# DW1000.net
KiCad netlist of a schematic drawn in Altium Designer
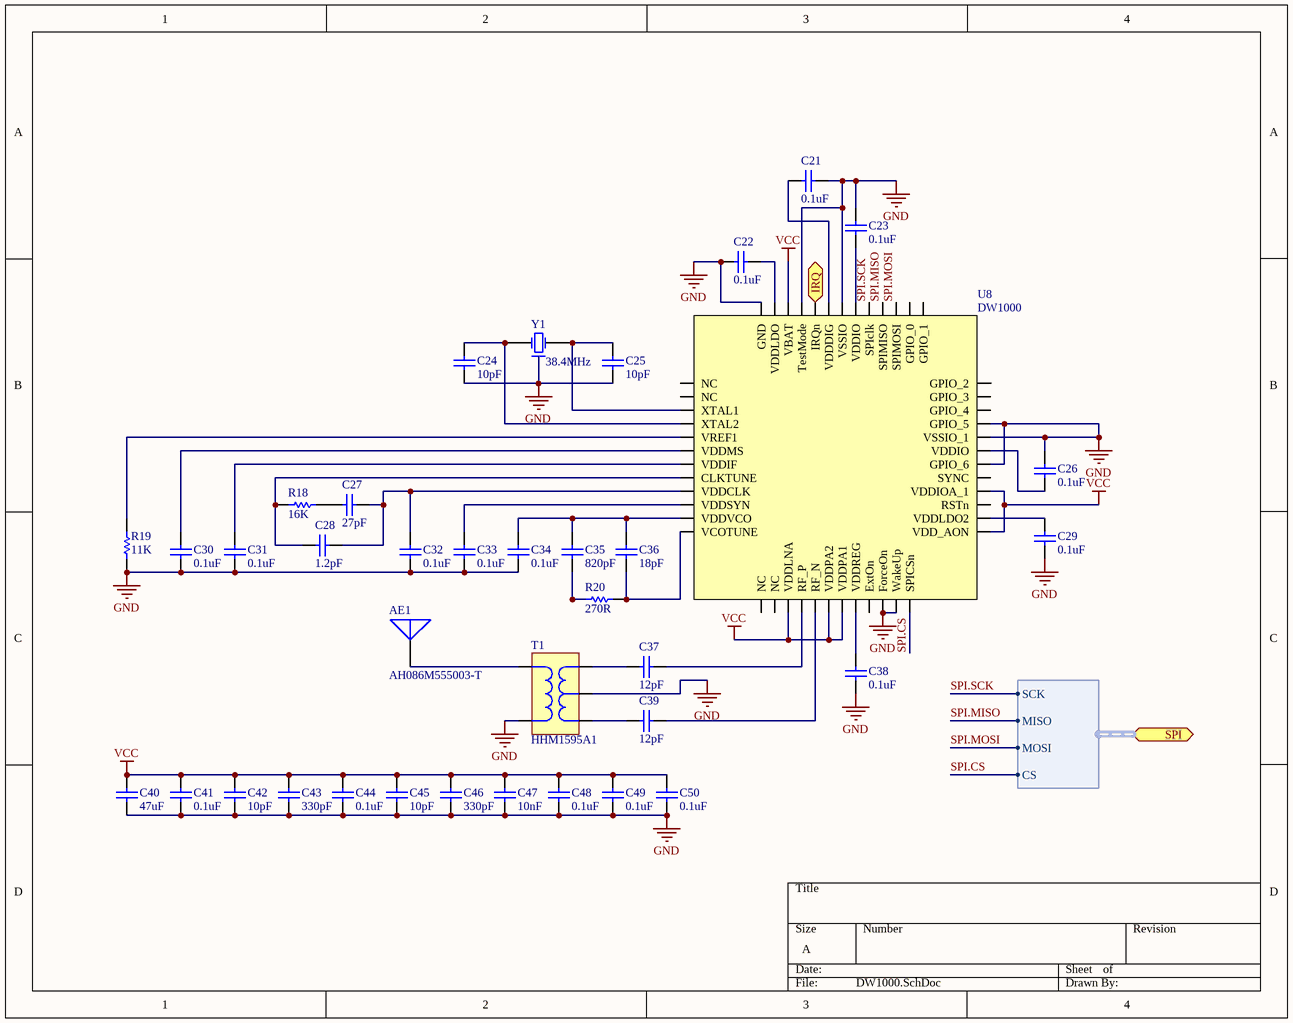
[diagram p0: DW1000.SchDoc]

(export (version "E")
  (design (tool "Eeschema 10.0.6"))
  (components
    (comp (ref "AE1")
      (value "AH086M555003-T")
      (footprint "AH086M555003-T")
      (fields (field (name "MANUFACTURER") "Taiyo Yuden"))
      (libsource (lib "Components") (part "AH086M555003-T"))
    )
    (comp (ref "C21")
      (value "0.1uF")
      (footprint "C0402[1005X55]")
      (description "0.1uF 6.3V 10% 0402 (1005 Metric)")
      (fields (field (name "PARTNUMBER") "GRM155R70J104KA01D") (field (name "MANUFACTURER") "Murata"))
      (libsource (lib "Capacitors") (part "CAP_0.1uF_6.3V_0402_10%"))
    )
    (comp (ref "C22")
      (value "0.1uF")
      (footprint "C0402[1005X55]")
      (description "0.1uF 6.3V 10% 0402 (1005 Metric)")
      (fields (field (name "PARTNUMBER") "GRM155R70J104KA01D") (field (name "MANUFACTURER") "Murata"))
      (libsource (lib "Capacitors") (part "CAP_0.1uF_6.3V_0402_10%"))
    )
    (comp (ref "C23")
      (value "0.1uF")
      (footprint "C0402[1005X55]")
      (description "0.1uF 6.3V 10% 0402 (1005 Metric)")
      (fields (field (name "PARTNUMBER") "GRM155R70J104KA01D") (field (name "MANUFACTURER") "Murata"))
      (libsource (lib "Capacitors") (part "CAP_0.1uF_6.3V_0402_10%"))
    )
    (comp (ref "C24")
      (value "10pF")
      (footprint "C0402[1005X55]")
      (description "10pF 50V 1% 0402 (1005 Metric)")
      (fields (field (name "PARTNUMBER") "GRM1555C1H100FA01D") (field (name "MANUFACTURER") "Murata"))
      (libsource (lib "Capacitors") (part "CAP_10pF_50V_0402_1%"))
    )
    (comp (ref "C25")
      (value "10pF")
      (footprint "C0402[1005X55]")
      (description "10pF 50V 1% 0402 (1005 Metric)")
      (fields (field (name "PARTNUMBER") "GRM1555C1H100FA01D") (field (name "MANUFACTURER") "Murata"))
      (libsource (lib "Capacitors") (part "CAP_10pF_50V_0402_1%"))
    )
    (comp (ref "C26")
      (value "0.1uF")
      (footprint "C0402[1005X55]")
      (description "0.1uF 6.3V 10% 0402 (1005 Metric)")
      (fields (field (name "PARTNUMBER") "GRM155R70J104KA01D") (field (name "MANUFACTURER") "Murata"))
      (libsource (lib "Capacitors") (part "CAP_0.1uF_6.3V_0402_10%"))
    )
    (comp (ref "C27")
      (value "27pF")
      (footprint "C0402[1005X55]")
      (description "27pF 50V 1% 0402 (1005 Metric)")
      (fields (field (name "PARTNUMBER") "GRM1555C1H270FA01D") (field (name "MANUFACTURER") "Murata"))
      (libsource (lib "Capacitors") (part "CAP_27pF_50V_0402_1%"))
    )
    (comp (ref "C28")
      (value "1.2pF")
      (footprint "C0402[1005X55]")
      (description "1.2pF 50V 0.05pF 0402 (1005 Metric)")
      (fields (field (name "PARTNUMBER") "GRM1555C1H1R2WA01D") (field (name "MANUFACTURER") "Murata"))
      (libsource (lib "Capacitors") (part "CAP_1.2pF_50V_0402_0.05pF"))
    )
    (comp (ref "C29")
      (value "0.1uF")
      (footprint "C0402[1005X55]")
      (description "0.1uF 6.3V 10% 0402 (1005 Metric)")
      (fields (field (name "PARTNUMBER") "GRM155R70J104KA01D") (field (name "MANUFACTURER") "Murata"))
      (libsource (lib "Capacitors") (part "CAP_0.1uF_6.3V_0402_10%"))
    )
    (comp (ref "C30")
      (value "0.1uF")
      (footprint "C0402[1005X55]")
      (description "0.1uF 6.3V 10% 0402 (1005 Metric)")
      (fields (field (name "PARTNUMBER") "GRM155R70J104KA01D") (field (name "MANUFACTURER") "Murata"))
      (libsource (lib "Capacitors") (part "CAP_0.1uF_6.3V_0402_10%"))
    )
    (comp (ref "C31")
      (value "0.1uF")
      (footprint "C0402[1005X55]")
      (description "0.1uF 6.3V 10% 0402 (1005 Metric)")
      (fields (field (name "PARTNUMBER") "GRM155R70J104KA01D") (field (name "MANUFACTURER") "Murata"))
      (libsource (lib "Capacitors") (part "CAP_0.1uF_6.3V_0402_10%"))
    )
    (comp (ref "C32")
      (value "0.1uF")
      (footprint "C0402[1005X55]")
      (description "0.1uF 6.3V 10% 0402 (1005 Metric)")
      (fields (field (name "PARTNUMBER") "GRM155R70J104KA01D") (field (name "MANUFACTURER") "Murata"))
      (libsource (lib "Capacitors") (part "CAP_0.1uF_6.3V_0402_10%"))
    )
    (comp (ref "C33")
      (value "0.1uF")
      (footprint "C0402[1005X55]")
      (description "0.1uF 6.3V 10% 0402 (1005 Metric)")
      (fields (field (name "PARTNUMBER") "GRM155R70J104KA01D") (field (name "MANUFACTURER") "Murata"))
      (libsource (lib "Capacitors") (part "CAP_0.1uF_6.3V_0402_10%"))
    )
    (comp (ref "C34")
      (value "0.1uF")
      (footprint "C0402[1005X55]")
      (description "0.1uF 6.3V 10% 0402 (1005 Metric)")
      (fields (field (name "PARTNUMBER") "GRM155R70J104KA01D") (field (name "MANUFACTURER") "Murata"))
      (libsource (lib "Capacitors") (part "CAP_0.1uF_6.3V_0402_10%"))
    )
    (comp (ref "C35")
      (value "820pF")
      (footprint "C0402[1005X55]")
      (description "820pF 50V 5% 0402 (1005 Metric)")
      (fields (field (name "PARTNUMBER") "GRM1555C1H821JA01D") (field (name "MANUFACTURER") "Murata"))
      (libsource (lib "Capacitors") (part "CAP_820pF_50V_0402_5%"))
    )
    (comp (ref "C36")
      (value "18pF")
      (footprint "C0402[1005X55]")
      (description "18pF 50V 1% 0402 (1005 Metric)")
      (fields (field (name "PARTNUMBER") "GRM1555C1H180FA01D") (field (name "MANUFACTURER") "Murata"))
      (libsource (lib "Capacitors") (part "CAP_18pF_50V_0402_1%"))
    )
    (comp (ref "C37")
      (value "12pF")
      (footprint "C0402[1005X55]")
      (description "12pF 50V 5% 0402 (1005 Metric)")
      (fields (field (name "PARTNUMBER") "GRM1555C1H120JA01D") (field (name "MANUFACTURER") "Murata"))
      (libsource (lib "Capacitors") (part "CAP_12pF_50V_0402_5%"))
    )
    (comp (ref "C38")
      (value "0.1uF")
      (footprint "C0402[1005X55]")
      (description "0.1uF 6.3V 10% 0402 (1005 Metric)")
      (fields (field (name "PARTNUMBER") "GRM155R70J104KA01D") (field (name "MANUFACTURER") "Murata"))
      (libsource (lib "Capacitors") (part "CAP_0.1uF_6.3V_0402_10%"))
    )
    (comp (ref "C39")
      (value "12pF")
      (footprint "C0402[1005X55]")
      (description "12pF 50V 5% 0402 (1005 Metric)")
      (fields (field (name "PARTNUMBER") "GRM1555C1H120JA01D") (field (name "MANUFACTURER") "Murata"))
      (libsource (lib "Capacitors") (part "CAP_12pF_50V_0402_5%"))
    )
    (comp (ref "C40")
      (value "47uF")
      (footprint "C1206[3216X160]")
      (description "47uF 6.3V 10% 1206 (3216 Metric)")
      (fields (field (name "PARTNUMBER") "GRM31CR60J476KE19L") (field (name "MANUFACTURER") "Murata"))
      (libsource (lib "Capacitors") (part "CAP_47uF_6.3V_1206_10%"))
    )
    (comp (ref "C41")
      (value "0.1uF")
      (footprint "C0402[1005X55]")
      (description "0.1uF 6.3V 10% 0402 (1005 Metric)")
      (fields (field (name "PARTNUMBER") "GRM155R70J104KA01D") (field (name "MANUFACTURER") "Murata"))
      (libsource (lib "Capacitors") (part "CAP_0.1uF_6.3V_0402_10%"))
    )
    (comp (ref "C42")
      (value "10pF")
      (footprint "C0402[1005X55]")
      (description "10pF 50V 1% 0402 (1005 Metric)")
      (fields (field (name "PARTNUMBER") "GRM1555C1H100FA01D") (field (name "MANUFACTURER") "Murata"))
      (libsource (lib "Capacitors") (part "CAP_10pF_50V_0402_1%"))
    )
    (comp (ref "C43")
      (value "330pF")
      (footprint "C0402[1005X55]")
      (description "330pF 50V 5% 0402 (1005 Metric)")
      (fields (field (name "PARTNUMBER") "GRM1555C1H331JA01D") (field (name "MANUFACTURER") "Murata"))
      (libsource (lib "Capacitors") (part "CAP_330pF_50V_0402_5%"))
    )
    (comp (ref "C44")
      (value "0.1uF")
      (footprint "C0402[1005X55]")
      (description "0.1uF 6.3V 10% 0402 (1005 Metric)")
      (fields (field (name "PARTNUMBER") "GRM155R70J104KA01D") (field (name "MANUFACTURER") "Murata"))
      (libsource (lib "Capacitors") (part "CAP_0.1uF_6.3V_0402_10%"))
    )
    (comp (ref "C45")
      (value "10pF")
      (footprint "C0402[1005X55]")
      (description "10pF 50V 1% 0402 (1005 Metric)")
      (fields (field (name "PARTNUMBER") "GRM1555C1H100FA01D") (field (name "MANUFACTURER") "Murata"))
      (libsource (lib "Capacitors") (part "CAP_10pF_50V_0402_1%"))
    )
    (comp (ref "C46")
      (value "330pF")
      (footprint "C0402[1005X55]")
      (description "330pF 50V 5% 0402 (1005 Metric)")
      (fields (field (name "PARTNUMBER") "GRM1555C1H331JA01D") (field (name "MANUFACTURER") "Murata"))
      (libsource (lib "Capacitors") (part "CAP_330pF_50V_0402_5%"))
    )
    (comp (ref "C47")
      (value "10nF")
      (footprint "C0402[1005X55]")
      (description "10nF 50V 10% 0402 (1005 Metric)")
      (fields (field (name "PARTNUMBER") "GCM155R71H103KA55D") (field (name "MANUFACTURER") "Murata"))
      (libsource (lib "Capacitors") (part "CAP_10nF_50V_0402_10%"))
    )
    (comp (ref "C48")
      (value "0.1uF")
      (footprint "C0402[1005X55]")
      (description "0.1uF 6.3V 10% 0402 (1005 Metric)")
      (fields (field (name "PARTNUMBER") "GRM155R70J104KA01D") (field (name "MANUFACTURER") "Murata"))
      (libsource (lib "Capacitors") (part "CAP_0.1uF_6.3V_0402_10%"))
    )
    (comp (ref "C49")
      (value "0.1uF")
      (footprint "C0402[1005X55]")
      (description "0.1uF 6.3V 10% 0402 (1005 Metric)")
      (fields (field (name "PARTNUMBER") "GRM155R70J104KA01D") (field (name "MANUFACTURER") "Murata"))
      (libsource (lib "Capacitors") (part "CAP_0.1uF_6.3V_0402_10%"))
    )
    (comp (ref "C50")
      (value "0.1uF")
      (footprint "C0402[1005X55]")
      (description "0.1uF 6.3V 10% 0402 (1005 Metric)")
      (fields (field (name "PARTNUMBER") "GRM155R70J104KA01D") (field (name "MANUFACTURER") "Murata"))
      (libsource (lib "Capacitors") (part "CAP_0.1uF_6.3V_0402_10%"))
    )
    (comp (ref "R18")
      (value "16K")
      (footprint "R0402[1005]")
      (description "16K 0.063W 1% 0402 (1005 Metric)")
      (fields (field (name "MANUFACTURER") "KOA Speer") (field (name "PARTNUMBER") "RK73H1ETTP1602F"))
      (libsource (lib "Resistors") (part "RES_16K_0402_1%"))
    )
    (comp (ref "R19")
      (value "11K")
      (footprint "R0402[1005]")
      (description "11K 0.063W 1% 0402 (1005 Metric)")
      (fields (field (name "MANUFACTURER") "KOA Speer") (field (name "PARTNUMBER") "RK73H1ETTP1102F"))
      (libsource (lib "Resistors") (part "RES_11K_0402_1%"))
    )
    (comp (ref "R20")
      (value "270R")
      (footprint "R0402[1005]")
      (description "270R 0.063W 1% 0402 (1005 Metric)")
      (fields (field (name "MANUFACTURER") "KOA Speer") (field (name "PARTNUMBER") "RK73H1ETTP2700F"))
      (libsource (lib "Resistors") (part "RES_270R_0402_1%"))
    )
    (comp (ref "T1")
      (value "HHM1595A1")
      (footprint "HHM1595A1")
      (fields (field (name "MANUFACTURER") "TDK"))
      (libsource (lib "Components") (part "HHM1595A1"))
    )
    (comp (ref "U8")
      (value "DW1000")
      (footprint "QFN-48")
      (description "UWB DW1000")
      (fields (field (name "PART NUMBER") "DW1000-I-TR13") (field (name "MANUFACTURER") "Decawave Limited"))
      (libsource (lib "ICs") (part "DW1000"))
    )
    (comp (ref "Y1")
      (value "38.4MHz")
      (footprint "ABRA-ABM10")
      (fields (field (name "PARTNUMBER") "ABM10-165-38.400MHZ-T3") (field (name "MANUFACTURER") "ABRACON"))
      (libsource (lib "Components") (part "ABM10-165-38.400MHZ-T3"))
    )
  )
  (nets
    (net (code "2") (name "/IRQ") (class "Default")
      (node (ref "U8") (pin "45") (pinfunction "IRQn_45") (pintype "passive"))
    )
    (net (code "3") (name "/SPI.CS") (class "Default")
      (node (ref "U8") (pin "24") (pinfunction "SPICSn_24") (pintype "passive"))
    )
    (net (code "4") (name "/SPI.MISO") (class "Default")
      (node (ref "U8") (pin "40") (pinfunction "SPIMISO_40") (pintype "passive"))
    )
    (net (code "5") (name "/SPI.MOSI") (class "Default")
      (node (ref "U8") (pin "39") (pinfunction "SPIMOSI_39") (pintype "passive"))
    )
    (net (code "6") (name "/SPI.SCK") (class "Default")
      (node (ref "U8") (pin "41") (pinfunction "SPIclk_41") (pintype "passive"))
    )
    (net (code "8") (name "GND") (class "Default")
      (node (ref "C21") (pin "1") (pinfunction "1_1") (pintype "passive"))
      (node (ref "C22") (pin "2") (pinfunction "2_2") (pintype "passive"))
      (node (ref "C23") (pin "2") (pinfunction "2_2") (pintype "passive"))
      (node (ref "C24") (pin "1") (pinfunction "1_1") (pintype "passive"))
      (node (ref "C25") (pin "1") (pinfunction "1_1") (pintype "passive"))
      (node (ref "C26") (pin "2") (pinfunction "2_2") (pintype "passive"))
      (node (ref "C29") (pin "1") (pinfunction "1_1") (pintype "passive"))
      (node (ref "C30") (pin "1") (pinfunction "1_1") (pintype "passive"))
      (node (ref "C31") (pin "1") (pinfunction "1_1") (pintype "passive"))
      (node (ref "C32") (pin "1") (pinfunction "1_1") (pintype "passive"))
      (node (ref "C33") (pin "1") (pinfunction "1_1") (pintype "passive"))
      (node (ref "C34") (pin "1") (pinfunction "1_1") (pintype "passive"))
      (node (ref "C38") (pin "1") (pinfunction "1_1") (pintype "passive"))
      (node (ref "C40") (pin "1") (pinfunction "1_1") (pintype "passive"))
      (node (ref "C41") (pin "1") (pinfunction "1_1") (pintype "passive"))
      (node (ref "C42") (pin "1") (pinfunction "1_1") (pintype "passive"))
      (node (ref "C43") (pin "1") (pinfunction "1_1") (pintype "passive"))
      (node (ref "C44") (pin "1") (pinfunction "1_1") (pintype "passive"))
      (node (ref "C45") (pin "1") (pinfunction "1_1") (pintype "passive"))
      (node (ref "C46") (pin "1") (pinfunction "1_1") (pintype "passive"))
      (node (ref "C47") (pin "1") (pinfunction "1_1") (pintype "passive"))
      (node (ref "C48") (pin "1") (pinfunction "1_1") (pintype "passive"))
      (node (ref "C49") (pin "1") (pinfunction "1_1") (pintype "passive"))
      (node (ref "C50") (pin "1") (pinfunction "1_1") (pintype "passive"))
      (node (ref "R19") (pin "1") (pinfunction "1_1") (pintype "passive"))
      (node (ref "T1") (pin "2") (pinfunction "2_2") (pintype "passive"))
      (node (ref "T1") (pin "5") (pinfunction "5_5") (pintype "passive"))
      (node (ref "U8") (pin "22") (pinfunction "ForceOn_22") (pintype "passive"))
      (node (ref "U8") (pin "23") (pinfunction "WakeUp_23") (pintype "passive"))
      (node (ref "U8") (pin "30") (pinfunction "GPIO_6_30") (pintype "passive"))
      (node (ref "U8") (pin "32") (pinfunction "VSSIO_1_32") (pintype "passive"))
      (node (ref "U8") (pin "33") (pinfunction "GPIO_5_33") (pintype "passive"))
      (node (ref "U8") (pin "43") (pinfunction "VSSIO_43") (pintype "passive"))
      (node (ref "U8") (pin "46") (pinfunction "TestMode_46") (pintype "passive"))
      (node (ref "U8") (pin "49") (pinfunction "GND_49") (pintype "passive"))
      (node (ref "Y1") (pin "2") (pinfunction "2_2") (pintype "passive"))
    )
    (net (code "9") (name "Net-(AE1-Pad1)") (class "Default")
      (node (ref "AE1") (pin "1") (pinfunction "1_1") (pintype "passive"))
      (node (ref "T1") (pin "1") (pinfunction "1_1") (pintype "passive"))
    )
    (net (code "10") (name "Net-(C23-Pad1)") (class "Default")
      (node (ref "C23") (pin "1") (pinfunction "1_1") (pintype "passive"))
      (node (ref "U8") (pin "42") (pinfunction "VDDIO_42") (pintype "passive"))
    )
    (net (code "11") (name "Net-(C26-Pad1)") (class "Default")
      (node (ref "C26") (pin "1") (pinfunction "1_1") (pintype "passive"))
      (node (ref "U8") (pin "31") (pinfunction "VDDIO_31") (pintype "passive"))
    )
    (net (code "12") (name "Net-(C27-Pad2)") (class "Default")
      (node (ref "C27") (pin "2") (pinfunction "2_2") (pintype "passive"))
      (node (ref "R18") (pin "1") (pinfunction "1_1") (pintype "passive"))
    )
    (net (code "13") (name "Net-(C35-Pad1)") (class "Default")
      (node (ref "C35") (pin "1") (pinfunction "1_1") (pintype "passive"))
      (node (ref "R20") (pin "1") (pinfunction "1_1") (pintype "passive"))
    )
    (net (code "14") (name "Net-(C37-Pad1)") (class "Default")
      (node (ref "C37") (pin "1") (pinfunction "1_1") (pintype "passive"))
      (node (ref "T1") (pin "4") (pinfunction "4_4") (pintype "passive"))
    )
    (net (code "15") (name "Net-(C39-Pad1)") (class "Default")
      (node (ref "C39") (pin "1") (pinfunction "1_1") (pintype "passive"))
      (node (ref "T1") (pin "3") (pinfunction "3_3") (pintype "passive"))
    )
    (net (code "16") (name "Net-(U8-CLKTUNE)") (class "Default")
      (node (ref "C28") (pin "2") (pinfunction "2_2") (pintype "passive"))
      (node (ref "R18") (pin "2") (pinfunction "2_2") (pintype "passive"))
      (node (ref "U8") (pin "8") (pinfunction "CLKTUNE_8") (pintype "passive"))
    )
    (net (code "17") (name "Net-(U8-RF_N)") (class "Default")
      (node (ref "C39") (pin "2") (pinfunction "2_2") (pintype "passive"))
      (node (ref "U8") (pin "17") (pinfunction "RF_N_17") (pintype "passive"))
    )
    (net (code "18") (name "Net-(U8-RF_P)") (class "Default")
      (node (ref "C37") (pin "2") (pinfunction "2_2") (pintype "passive"))
      (node (ref "U8") (pin "16") (pinfunction "RF_P_16") (pintype "passive"))
    )
    (net (code "19") (name "Net-(U8-VCOTUNE)") (class "Default")
      (node (ref "C36") (pin "1") (pinfunction "1_1") (pintype "passive"))
      (node (ref "R20") (pin "2") (pinfunction "2_2") (pintype "passive"))
      (node (ref "U8") (pin "12") (pinfunction "VCOTUNE_12") (pintype "passive"))
    )
    (net (code "20") (name "Net-(U8-VDDCLK)") (class "Default")
      (node (ref "C27") (pin "1") (pinfunction "1_1") (pintype "passive"))
      (node (ref "C28") (pin "1") (pinfunction "1_1") (pintype "passive"))
      (node (ref "C32") (pin "2") (pinfunction "2_2") (pintype "passive"))
      (node (ref "U8") (pin "9") (pinfunction "VDDCLK_9") (pintype "passive"))
    )
    (net (code "21") (name "Net-(U8-VDDDIG)") (class "Default")
      (node (ref "C21") (pin "2") (pinfunction "2_2") (pintype "passive"))
      (node (ref "U8") (pin "44") (pinfunction "VDDDIG_44") (pintype "passive"))
    )
    (net (code "22") (name "Net-(U8-VDDIF)") (class "Default")
      (node (ref "C31") (pin "2") (pinfunction "2_2") (pintype "passive"))
      (node (ref "U8") (pin "7") (pinfunction "VDDIF_7") (pintype "passive"))
    )
    (net (code "23") (name "Net-(U8-VDDLDO)") (class "Default")
      (node (ref "C22") (pin "1") (pinfunction "1_1") (pintype "passive"))
      (node (ref "U8") (pin "48") (pinfunction "VDDLDO_48") (pintype "passive"))
    )
    (net (code "24") (name "Net-(U8-VDDLDO2)") (class "Default")
      (node (ref "C29") (pin "2") (pinfunction "2_2") (pintype "passive"))
      (node (ref "U8") (pin "26") (pinfunction "VDDLDO2_26") (pintype "passive"))
    )
    (net (code "25") (name "Net-(U8-VDDMS)") (class "Default")
      (node (ref "C30") (pin "2") (pinfunction "2_2") (pintype "passive"))
      (node (ref "U8") (pin "6") (pinfunction "VDDMS_6") (pintype "passive"))
    )
    (net (code "26") (name "Net-(U8-VDDREG)") (class "Default")
      (node (ref "C38") (pin "2") (pinfunction "2_2") (pintype "passive"))
      (node (ref "U8") (pin "20") (pinfunction "VDDREG_20") (pintype "passive"))
    )
    (net (code "27") (name "Net-(U8-VDDSYN)") (class "Default")
      (node (ref "C33") (pin "2") (pinfunction "2_2") (pintype "passive"))
      (node (ref "U8") (pin "10") (pinfunction "VDDSYN_10") (pintype "passive"))
    )
    (net (code "28") (name "Net-(U8-VDDVCO)") (class "Default")
      (node (ref "C34") (pin "2") (pinfunction "2_2") (pintype "passive"))
      (node (ref "C35") (pin "2") (pinfunction "2_2") (pintype "passive"))
      (node (ref "C36") (pin "2") (pinfunction "2_2") (pintype "passive"))
      (node (ref "U8") (pin "11") (pinfunction "VDDVCO_11") (pintype "passive"))
    )
    (net (code "29") (name "Net-(U8-VREF1)") (class "Default")
      (node (ref "R19") (pin "2") (pinfunction "2_2") (pintype "passive"))
      (node (ref "U8") (pin "5") (pinfunction "VREF1_5") (pintype "passive"))
    )
    (net (code "30") (name "Net-(U8-XTAL1)") (class "Default")
      (node (ref "C25") (pin "2") (pinfunction "2_2") (pintype "passive"))
      (node (ref "U8") (pin "3") (pinfunction "XTAL1_3") (pintype "passive"))
      (node (ref "Y1") (pin "3") (pinfunction "X2_3") (pintype "passive"))
    )
    (net (code "31") (name "Net-(U8-XTAL2)") (class "Default")
      (node (ref "C24") (pin "2") (pinfunction "2_2") (pintype "passive"))
      (node (ref "U8") (pin "4") (pinfunction "XTAL2_4") (pintype "passive"))
      (node (ref "Y1") (pin "1") (pinfunction "X1_1") (pintype "passive"))
    )
    (net (code "32") (name "VCC") (class "Default")
      (node (ref "C40") (pin "2") (pinfunction "2_2") (pintype "passive"))
      (node (ref "C41") (pin "2") (pinfunction "2_2") (pintype "passive"))
      (node (ref "C42") (pin "2") (pinfunction "2_2") (pintype "passive"))
      (node (ref "C43") (pin "2") (pinfunction "2_2") (pintype "passive"))
      (node (ref "C44") (pin "2") (pinfunction "2_2") (pintype "passive"))
      (node (ref "C45") (pin "2") (pinfunction "2_2") (pintype "passive"))
      (node (ref "C46") (pin "2") (pinfunction "2_2") (pintype "passive"))
      (node (ref "C47") (pin "2") (pinfunction "2_2") (pintype "passive"))
      (node (ref "C48") (pin "2") (pinfunction "2_2") (pintype "passive"))
      (node (ref "C49") (pin "2") (pinfunction "2_2") (pintype "passive"))
      (node (ref "C50") (pin "2") (pinfunction "2_2") (pintype "passive"))
      (node (ref "U8") (pin "15") (pinfunction "VDDLNA_15") (pintype "passive"))
      (node (ref "U8") (pin "18") (pinfunction "VDDPA2_18") (pintype "passive"))
      (node (ref "U8") (pin "19") (pinfunction "VDDPA1_19") (pintype "passive"))
      (node (ref "U8") (pin "25") (pinfunction "VDD_AON_25") (pintype "passive"))
      (node (ref "U8") (pin "28") (pinfunction "VDDIOA_1_28") (pintype "passive"))
      (node (ref "U8") (pin "47") (pinfunction "VBAT_47") (pintype "passive"))
    )
    (net (code "33") (name "unconnected-(U8-ExtOn-Pad21)") (class "Default")
      (node (ref "U8") (pin "21") (pinfunction "ExtOn_21") (pintype "passive"))
    )
    (net (code "34") (name "unconnected-(U8-GPIO_0-Pad38)") (class "Default")
      (node (ref "U8") (pin "38") (pinfunction "GPIO_0_38") (pintype "passive"))
    )
    (net (code "35") (name "unconnected-(U8-GPIO_1-Pad37)") (class "Default")
      (node (ref "U8") (pin "37") (pinfunction "GPIO_1_37") (pintype "passive"))
    )
    (net (code "36") (name "unconnected-(U8-GPIO_2-Pad36)") (class "Default")
      (node (ref "U8") (pin "36") (pinfunction "GPIO_2_36") (pintype "passive"))
    )
    (net (code "37") (name "unconnected-(U8-GPIO_3-Pad35)") (class "Default")
      (node (ref "U8") (pin "35") (pinfunction "GPIO_3_35") (pintype "passive"))
    )
    (net (code "38") (name "unconnected-(U8-GPIO_4-Pad34)") (class "Default")
      (node (ref "U8") (pin "34") (pinfunction "GPIO_4_34") (pintype "passive"))
    )
    (net (code "39") (name "unconnected-(U8-NC-Pad1)") (class "Default")
      (node (ref "U8") (pin "1") (pinfunction "NC_1") (pintype "passive"))
    )
    (net (code "40") (name "unconnected-(U8-NC-Pad2)") (class "Default")
      (node (ref "U8") (pin "2") (pinfunction "NC_2") (pintype "passive"))
    )
    (net (code "41") (name "unconnected-(U8-NC-Pad13)") (class "Default")
      (node (ref "U8") (pin "13") (pinfunction "NC_13") (pintype "passive"))
    )
    (net (code "42") (name "unconnected-(U8-NC-Pad14)") (class "Default")
      (node (ref "U8") (pin "14") (pinfunction "NC_14") (pintype "passive"))
    )
    (net (code "43") (name "unconnected-(U8-RSTn-Pad27)") (class "Default")
      (node (ref "U8") (pin "27") (pinfunction "RSTn_27") (pintype "passive"))
    )
    (net (code "44") (name "unconnected-(U8-SYNC-Pad29)") (class "Default")
      (node (ref "U8") (pin "29") (pinfunction "SYNC_29") (pintype "passive"))
    )
  )
)
